# SHT40.net
KiCad netlist of a schematic drawn in Altium Designer
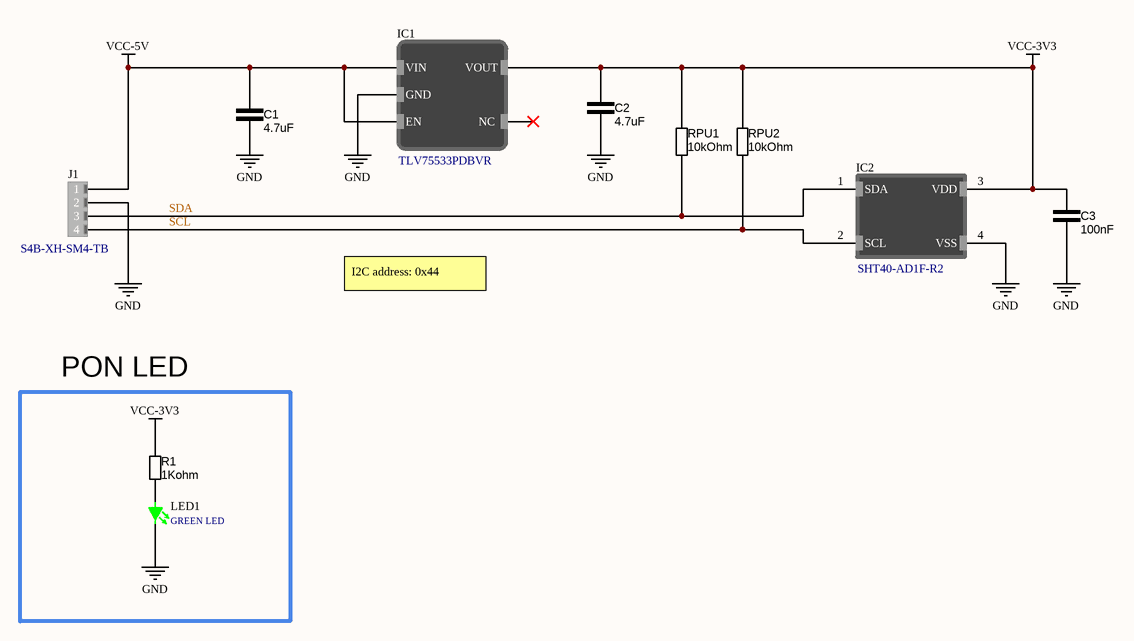
[diagram p0: SHT40.SchDoc]

(export (version "E")
  (design (tool "Eeschema 10.0.6"))
  (components
    (comp (ref "C1")
      (value "4.7uF")
      (footprint "CAP_0805")
      (description "4.7 µF ±10% 25V Ceramic Capacitor X5R 0805 (2012 Metric)")
      (fields
        (field (name "DIGIKEY PART NUMBER") "399-C0805C475K3PACTUCT-ND")
        (field (name "JLCPCB PART NUMBER") "C1779")
      )
      (libsource (lib "CapacitorsIntegrated") (part "C000003"))
    )
    (comp (ref "C2")
      (value "4.7uF")
      (footprint "CAP_0805")
      (description "4.7 µF ±10% 25V Ceramic Capacitor X5R 0805 (2012 Metric)")
      (fields
        (field (name "DIGIKEY PART NUMBER") "399-C0805C475K3PACTUCT-ND")
        (field (name "JLCPCB PART NUMBER") "C1779")
      )
      (libsource (lib "CapacitorsIntegrated") (part "C000003"))
    )
    (comp (ref "C3")
      (value "100nF")
      (footprint "CAP_0603")
      (description "0.1 µF ±10% 25V Ceramic Capacitor X7R 0603 (1608 Metric)")
      (fields
        (field (name "DIGIKEY PART NUMBER") "478-KAM15AR71E104KTCT-ND")
        (field (name "JLCPCB PART NUMBER") "C1590")
      )
      (libsource (lib "CapacitorsIntegrated") (part "C000007"))
    )
    (comp (ref "IC1")
      (value "TLV75533PDBVR")
      (footprint "SOT23_5")
      (description "Linear Voltage Regulator IC Positive Fixed 1 Output 500mA SOT-23-5")
      (fields
        (field (name "DIGIKEY PART NUMBER") "296-50411-1-ND")
        (field (name "MOUSER PART NUMBER") "595-TLV75533PDBVR")
      )
      (libsource (lib "IntegratedCircuits") (part "TLV75533PDBVR"))
    )
    (comp (ref "IC2")
      (value "SHT40-AD1F-R2")
      (footprint "SHT4X")
      (description "Humidity, Temperature 0 ~ 100% RH I2C ±1.8% RH 4 s Surface Mount")
      (fields
        (field (name "DIGIKEY PART NUMBER") "1649-SHT40-AD1F-R2CT-ND")
        (field (name "MOUSER PART NUMBER") "403-SHT40-AD1F-R2")
      )
      (libsource (lib "IntegratedCircuits") (part "SHT40-AD1F-R2"))
    )
    (comp (ref "J1")
      (value "S4B-XH-SM4-TB")
      (footprint "JST_S4B-XH-SM4-TB")
      (description "Connector Header Surface Mount, Right Angle 4 position 0.098\" (2.50mm)")
      (fields
        (field (name "DIGIKEY PART NUMBER") "455-2262-1-ND")
        (field (name "MOUSER PART NUMBER") "306-S4BXHSM4TBLFSN")
      )
      (libsource (lib "ElectroMechanical") (part "00000018"))
    )
    (comp (ref "LED1")
      (value "GREEN LED")
      (footprint "DIOC1608X04N")
      (description "LED GREEN DIFFUSED 0603 SMD")
      (libsource (lib "Miscellaneous_Lib1") (part "00000001"))
    )
    (comp (ref "R1")
      (value "1Kohm")
      (footprint "RES_0603")
      (description "RES 1K OHM 1% 1/10W 0603")
      (libsource (lib "ResistorsIntegrated") (part "R000004"))
    )
    (comp (ref "RPU1")
      (value "10kOhm")
      (footprint "RES_0603")
      (description "10 kOhms ±1% 0.125W, 1/8W Chip Resistor 0603 (1608 Metric) Anti-Sulfur Thin Film")
      (fields (field (name "DIGIKEY PART NUMBER") "MCT0603-10.0K-CFCT-ND"))
      (libsource (lib "ResistorsIntegrated") (part "R000001"))
    )
    (comp (ref "RPU2")
      (value "10kOhm")
      (footprint "RES_0603")
      (description "10 kOhms ±1% 0.125W, 1/8W Chip Resistor 0603 (1608 Metric) Anti-Sulfur Thin Film")
      (fields (field (name "DIGIKEY PART NUMBER") "MCT0603-10.0K-CFCT-ND"))
      (libsource (lib "ResistorsIntegrated") (part "R000001"))
    )
  )
  (nets
    (net (code "1") (name "/SCL") (class "Default")
      (node (ref "IC2") (pin "2") (pinfunction "SCL_2") (pintype "passive"))
      (node (ref "J1") (pin "4") (pinfunction "4_4") (pintype "passive"))
      (node (ref "RPU2") (pin "1") (pinfunction "1_1") (pintype "passive"))
    )
    (net (code "2") (name "/SDA") (class "Default")
      (node (ref "IC2") (pin "1") (pinfunction "SDA_1") (pintype "passive"))
      (node (ref "J1") (pin "3") (pinfunction "3_3") (pintype "passive"))
      (node (ref "RPU1") (pin "1") (pinfunction "1_1") (pintype "passive"))
    )
    (net (code "3") (name "GND") (class "Default")
      (node (ref "C1") (pin "1") (pinfunction "1_1") (pintype "passive"))
      (node (ref "C2") (pin "1") (pinfunction "1_1") (pintype "passive"))
      (node (ref "C3") (pin "1") (pinfunction "1_1") (pintype "passive"))
      (node (ref "IC1") (pin "2") (pinfunction "GND_2") (pintype "passive"))
      (node (ref "IC2") (pin "4") (pinfunction "VSS_4") (pintype "passive"))
      (node (ref "J1") (pin "2") (pinfunction "2_2") (pintype "passive"))
      (node (ref "LED1") (pin "2") (pinfunction "2_2") (pintype "passive"))
    )
    (net (code "4") (name "Net-(LED1-Pad1)") (class "Default")
      (node (ref "LED1") (pin "1") (pinfunction "1_1") (pintype "passive"))
      (node (ref "R1") (pin "1") (pinfunction "1_1") (pintype "passive"))
    )
    (net (code "5") (name "VCC-3V3") (class "Default")
      (node (ref "C2") (pin "2") (pinfunction "2_2") (pintype "passive"))
      (node (ref "C3") (pin "2") (pinfunction "2_2") (pintype "passive"))
      (node (ref "IC1") (pin "5") (pinfunction "VOUT_5") (pintype "passive"))
      (node (ref "IC2") (pin "3") (pinfunction "VDD_3") (pintype "passive"))
      (node (ref "R1") (pin "2") (pinfunction "2_2") (pintype "passive"))
      (node (ref "RPU1") (pin "2") (pinfunction "2_2") (pintype "passive"))
      (node (ref "RPU2") (pin "2") (pinfunction "2_2") (pintype "passive"))
    )
    (net (code "6") (name "VCC-5V") (class "Default")
      (node (ref "C1") (pin "2") (pinfunction "2_2") (pintype "passive"))
      (node (ref "IC1") (pin "1") (pinfunction "VIN_1") (pintype "passive"))
      (node (ref "IC1") (pin "3") (pinfunction "EN_3") (pintype "open_collector"))
      (node (ref "J1") (pin "1") (pinfunction "1_1") (pintype "passive"))
    )
    (net (code "7") (name "unconnected-(IC1-NC-Pad4)") (class "Default")
      (node (ref "IC1") (pin "4") (pinfunction "NC_4") (pintype "passive+no_connect"))
    )
  )
)
